# M119.net
KiCad netlist of a schematic drawn in EAGLE
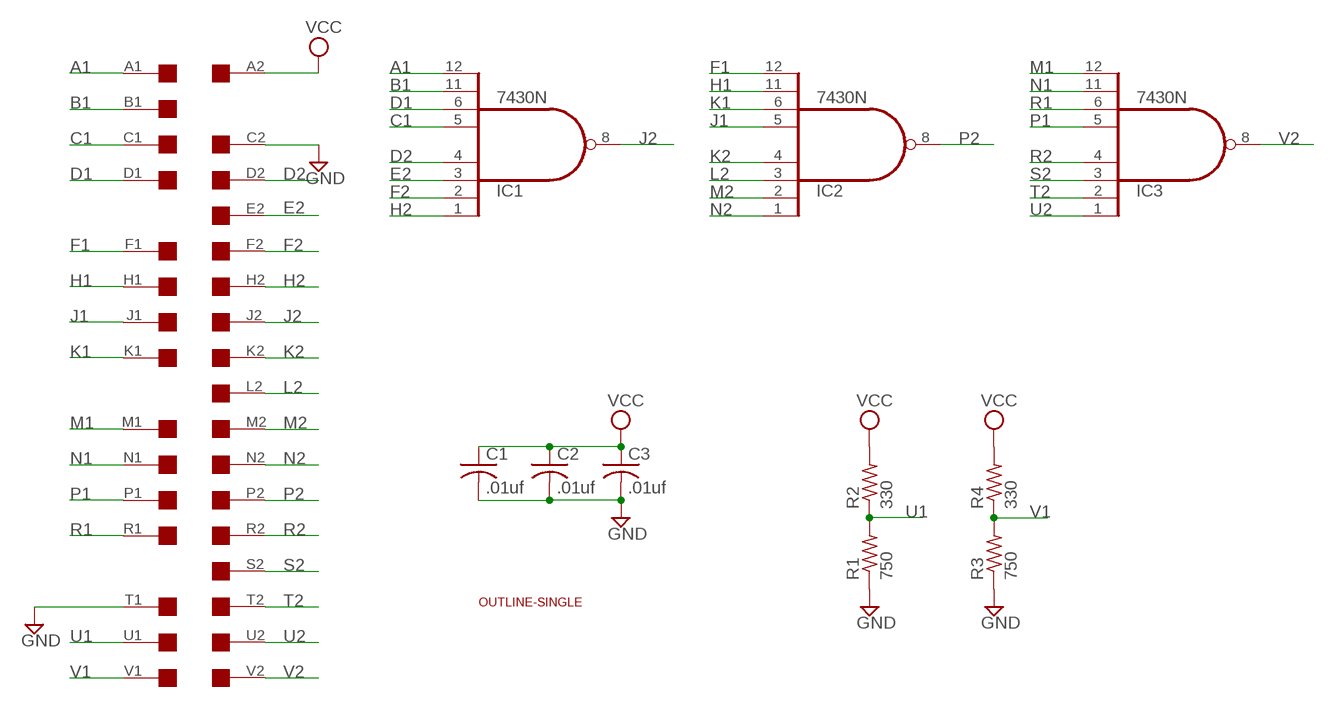
[diagram p0: schematic, sheet 1]

(export (version "E")
  (design (tool "Eeschema 10.0.6"))
  (components
    (comp (ref "C1")
      (value ".01uf")
      (footprint "eagle-import:C050-025X075")
      (libsource (lib "eagle-import") (part "C-US050-025X075"))
    )
    (comp (ref "C2")
      (value ".01uf")
      (footprint "eagle-import:C050-025X075")
      (libsource (lib "eagle-import") (part "C-US050-025X075"))
    )
    (comp (ref "C3")
      (value ".01uf")
      (footprint "eagle-import:C050-025X075")
      (libsource (lib "eagle-import") (part "C-US050-025X075"))
    )
    (comp (ref "IC1")
      (value "7430N")
      (footprint "eagle-import:DIL14")
      (libsource (lib "eagle-import") (part "7430N"))
    )
    (comp (ref "IC2")
      (value "7430N")
      (footprint "eagle-import:DIL14")
      (libsource (lib "eagle-import") (part "7430N"))
    )
    (comp (ref "IC3")
      (value "7430N")
      (footprint "eagle-import:DIL14")
      (libsource (lib "eagle-import") (part "7430N"))
    )
    (comp (ref "R1")
      (value "750")
      (footprint "eagle-import:0207_10")
      (libsource (lib "eagle-import") (part "R-US_0207/10"))
    )
    (comp (ref "R2")
      (value "330")
      (footprint "eagle-import:0207_10")
      (libsource (lib "eagle-import") (part "R-US_0207/10"))
    )
    (comp (ref "R3")
      (value "750")
      (footprint "eagle-import:0207_10")
      (libsource (lib "eagle-import") (part "R-US_0207/10"))
    )
    (comp (ref "R4")
      (value "330")
      (footprint "eagle-import:0207_10")
      (libsource (lib "eagle-import") (part "R-US_0207/10"))
    )
    (comp (ref "U$1")
      (value "OUTLINE-SINGLE")
      (footprint "eagle-import:SINGLE")
      (libsource (lib "eagle-import") (part "OUTLINE-SINGLE"))
    )
    (comp (ref "U$4")
      (value "SINGLE")
      (footprint "eagle-import:EDGE-CON2")
      (libsource (lib "eagle-import") (part "SINGLE"))
    )
  )
  (nets
    (net (code "1") (name "/A1") (class "Default")
      (node (ref "IC1") (pin "12") (pinfunction "I7_12") (pintype "input"))
      (node (ref "U$4") (pin "A1") (pinfunction "1_A1") (pintype "bidirectional"))
    )
    (net (code "2") (name "/B1") (class "Default")
      (node (ref "IC1") (pin "11") (pinfunction "I6_11") (pintype "input"))
      (node (ref "U$4") (pin "B1") (pinfunction "1_B1") (pintype "bidirectional"))
    )
    (net (code "3") (name "/C1") (class "Default")
      (node (ref "IC1") (pin "5") (pinfunction "I4_5") (pintype "input"))
      (node (ref "U$4") (pin "C1") (pinfunction "1_C1") (pintype "bidirectional"))
    )
    (net (code "4") (name "/D1") (class "Default")
      (node (ref "IC1") (pin "6") (pinfunction "I5_6") (pintype "input"))
      (node (ref "U$4") (pin "D1") (pinfunction "1_D1") (pintype "bidirectional"))
    )
    (net (code "5") (name "/D2") (class "Default")
      (node (ref "IC1") (pin "4") (pinfunction "I3_4") (pintype "input"))
      (node (ref "U$4") (pin "D2") (pinfunction "1_D2") (pintype "bidirectional"))
    )
    (net (code "6") (name "/E2") (class "Default")
      (node (ref "IC1") (pin "3") (pinfunction "I2_3") (pintype "input"))
      (node (ref "U$4") (pin "E2") (pinfunction "1_E2") (pintype "bidirectional"))
    )
    (net (code "7") (name "/F1") (class "Default")
      (node (ref "IC2") (pin "12") (pinfunction "I7_12") (pintype "input"))
      (node (ref "U$4") (pin "F1") (pinfunction "1_F1") (pintype "bidirectional"))
    )
    (net (code "8") (name "/F2") (class "Default")
      (node (ref "IC1") (pin "2") (pinfunction "I1_2") (pintype "input"))
      (node (ref "U$4") (pin "F2") (pinfunction "1_F2") (pintype "bidirectional"))
    )
    (net (code "9") (name "/H1") (class "Default")
      (node (ref "IC2") (pin "11") (pinfunction "I6_11") (pintype "input"))
      (node (ref "U$4") (pin "H1") (pinfunction "1_H1") (pintype "bidirectional"))
    )
    (net (code "10") (name "/H2") (class "Default")
      (node (ref "IC1") (pin "1") (pinfunction "I0_1") (pintype "input"))
      (node (ref "U$4") (pin "H2") (pinfunction "1_H2") (pintype "bidirectional"))
    )
    (net (code "11") (name "/J1") (class "Default")
      (node (ref "IC2") (pin "5") (pinfunction "I4_5") (pintype "input"))
      (node (ref "U$4") (pin "J1") (pinfunction "1_J1") (pintype "bidirectional"))
    )
    (net (code "12") (name "/J2") (class "Default")
      (node (ref "IC1") (pin "8") (pinfunction "O_8") (pintype "output"))
      (node (ref "U$4") (pin "J2") (pinfunction "1_J2") (pintype "bidirectional"))
    )
    (net (code "13") (name "/K1") (class "Default")
      (node (ref "IC2") (pin "6") (pinfunction "I5_6") (pintype "input"))
      (node (ref "U$4") (pin "K1") (pinfunction "1_K1") (pintype "bidirectional"))
    )
    (net (code "14") (name "/K2") (class "Default")
      (node (ref "IC2") (pin "4") (pinfunction "I3_4") (pintype "input"))
      (node (ref "U$4") (pin "K2") (pinfunction "1_K2") (pintype "bidirectional"))
    )
    (net (code "15") (name "/L2") (class "Default")
      (node (ref "IC2") (pin "3") (pinfunction "I2_3") (pintype "input"))
      (node (ref "U$4") (pin "L2") (pinfunction "1_L2") (pintype "bidirectional"))
    )
    (net (code "16") (name "/M1") (class "Default")
      (node (ref "IC3") (pin "12") (pinfunction "I7_12") (pintype "input"))
      (node (ref "U$4") (pin "M1") (pinfunction "1_M1") (pintype "bidirectional"))
    )
    (net (code "17") (name "/M2") (class "Default")
      (node (ref "IC2") (pin "2") (pinfunction "I1_2") (pintype "input"))
      (node (ref "U$4") (pin "M2") (pinfunction "1_M2") (pintype "bidirectional"))
    )
    (net (code "18") (name "/N1") (class "Default")
      (node (ref "IC3") (pin "11") (pinfunction "I6_11") (pintype "input"))
      (node (ref "U$4") (pin "N1") (pinfunction "1_N1") (pintype "bidirectional"))
    )
    (net (code "19") (name "/N2") (class "Default")
      (node (ref "IC2") (pin "1") (pinfunction "I0_1") (pintype "input"))
      (node (ref "U$4") (pin "N2") (pinfunction "1_N2") (pintype "bidirectional"))
    )
    (net (code "20") (name "/P1") (class "Default")
      (node (ref "IC3") (pin "5") (pinfunction "I4_5") (pintype "input"))
      (node (ref "U$4") (pin "P1") (pinfunction "1_P1") (pintype "bidirectional"))
    )
    (net (code "21") (name "/P2") (class "Default")
      (node (ref "IC2") (pin "8") (pinfunction "O_8") (pintype "output"))
      (node (ref "U$4") (pin "P2") (pinfunction "1_P2") (pintype "bidirectional"))
    )
    (net (code "22") (name "/R1") (class "Default")
      (node (ref "IC3") (pin "6") (pinfunction "I5_6") (pintype "input"))
      (node (ref "U$4") (pin "R1") (pinfunction "1_R1") (pintype "bidirectional"))
    )
    (net (code "23") (name "/R2") (class "Default")
      (node (ref "IC3") (pin "4") (pinfunction "I3_4") (pintype "input"))
      (node (ref "U$4") (pin "R2") (pinfunction "1_R2") (pintype "bidirectional"))
    )
    (net (code "24") (name "/S2") (class "Default")
      (node (ref "IC3") (pin "3") (pinfunction "I2_3") (pintype "input"))
      (node (ref "U$4") (pin "S2") (pinfunction "1_S2") (pintype "bidirectional"))
    )
    (net (code "25") (name "/T2") (class "Default")
      (node (ref "IC3") (pin "2") (pinfunction "I1_2") (pintype "input"))
      (node (ref "U$4") (pin "T2") (pinfunction "1_T2") (pintype "bidirectional"))
    )
    (net (code "26") (name "/U1") (class "Default")
      (node (ref "R1") (pin "2") (pinfunction "2_2") (pintype "passive"))
      (node (ref "R2") (pin "1") (pinfunction "1_1") (pintype "passive"))
      (node (ref "U$4") (pin "U1") (pinfunction "1_U1") (pintype "bidirectional"))
    )
    (net (code "27") (name "/U2") (class "Default")
      (node (ref "IC3") (pin "1") (pinfunction "I0_1") (pintype "input"))
      (node (ref "U$4") (pin "U2") (pinfunction "1_U2") (pintype "bidirectional"))
    )
    (net (code "28") (name "/V1") (class "Default")
      (node (ref "R3") (pin "2") (pinfunction "2_2") (pintype "passive"))
      (node (ref "R4") (pin "1") (pinfunction "1_1") (pintype "passive"))
      (node (ref "U$4") (pin "V1") (pinfunction "1_V1") (pintype "bidirectional"))
    )
    (net (code "29") (name "/V2") (class "Default")
      (node (ref "IC3") (pin "8") (pinfunction "O_8") (pintype "output"))
      (node (ref "U$4") (pin "V2") (pinfunction "1_V2") (pintype "bidirectional"))
    )
    (net (code "30") (name "GND") (class "Default")
      (node (ref "C1") (pin "2") (pinfunction "2_2") (pintype "passive"))
      (node (ref "C2") (pin "2") (pinfunction "2_2") (pintype "passive"))
      (node (ref "C3") (pin "2") (pinfunction "2_2") (pintype "passive"))
      (node (ref "R1") (pin "1") (pinfunction "1_1") (pintype "passive"))
      (node (ref "R3") (pin "1") (pinfunction "1_1") (pintype "passive"))
      (node (ref "U$4") (pin "C2") (pinfunction "1_C2") (pintype "bidirectional"))
      (node (ref "U$4") (pin "T1") (pinfunction "1_T1") (pintype "bidirectional"))
    )
    (net (code "31") (name "VCC") (class "Default")
      (node (ref "C1") (pin "1") (pinfunction "1_1") (pintype "passive"))
      (node (ref "C2") (pin "1") (pinfunction "1_1") (pintype "passive"))
      (node (ref "C3") (pin "1") (pinfunction "1_1") (pintype "passive"))
      (node (ref "R2") (pin "2") (pinfunction "2_2") (pintype "passive"))
      (node (ref "R4") (pin "2") (pinfunction "2_2") (pintype "passive"))
      (node (ref "U$4") (pin "A2") (pinfunction "1_A2") (pintype "bidirectional"))
    )
  )
)
